# Controller_v6_1.net
KiCad netlist of a schematic drawn in Altium Designer
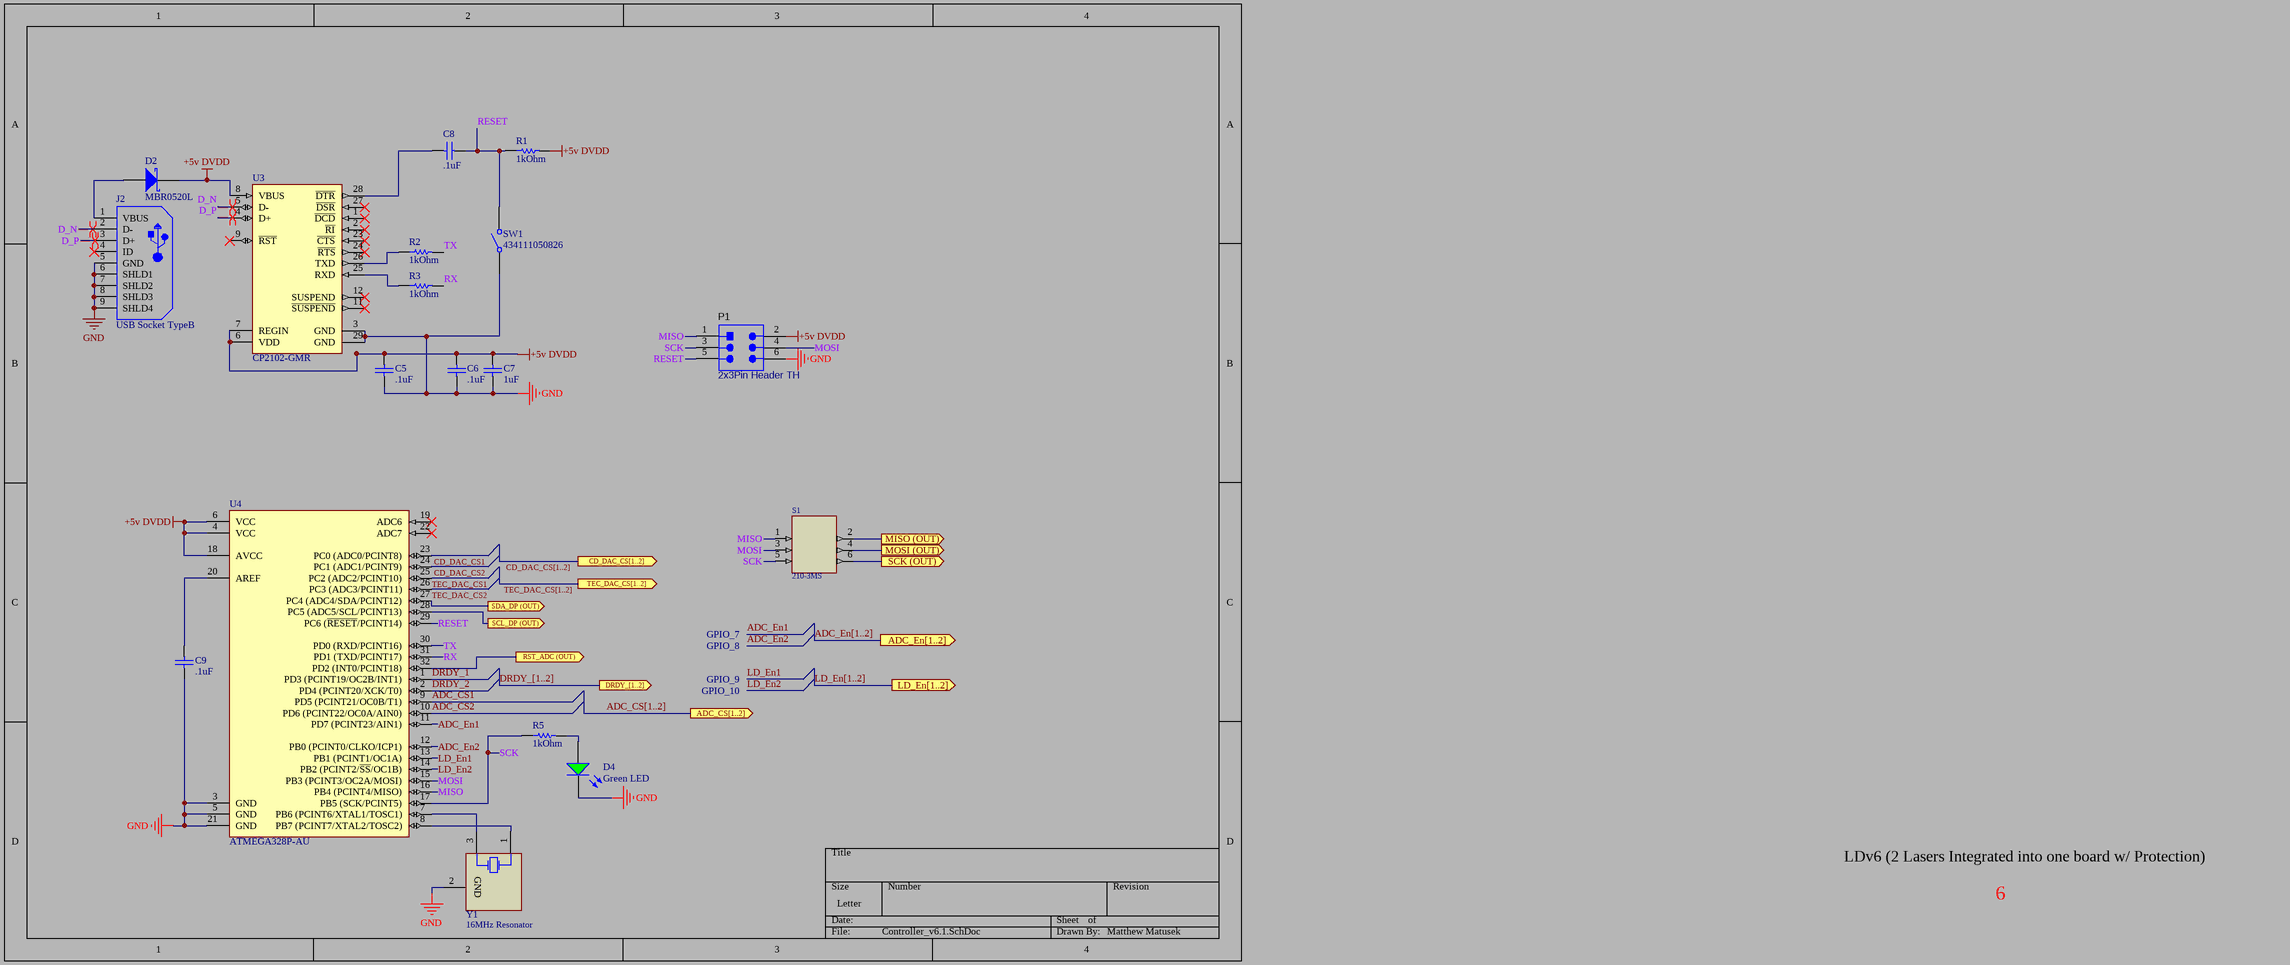
[diagram p0: Controller_v6.1.SchDoc]

(export (version "E")
  (design (tool "Eeschema 10.0.6"))
  (components
    (comp (ref "C5")
      (value ".1uF")
      (footprint "CAPC1608X90X35ML15T15")
      (fields
        (field (name "PART NUMBER") "06033D104MAT2A")
        (field (name "MANUFACTURER") "AVX Interconnect / Elco")
      )
      (libsource (lib "0.1uF Cap 0603") (part "CMP-2006-04192-1"))
    )
    (comp (ref "C6")
      (value ".1uF")
      (footprint "CAPC1608X90X35ML15T15")
      (fields
        (field (name "PART NUMBER") "06033D104MAT2A")
        (field (name "MANUFACTURER") "AVX Interconnect / Elco")
      )
      (libsource (lib "0.1uF Cap 0603") (part "CMP-2006-04192-1"))
    )
    (comp (ref "C7")
      (value "1uF")
      (footprint "CAPC1608X90X35ML15T15")
      (fields
        (field (name "PART NUMBER") "06036D105KAT2A")
        (field (name "MANUFACTURER") "AVX Interconnect / Elco")
      )
      (libsource (lib "1uF Cap 0603") (part "CMP-2006-04474-1"))
    )
    (comp (ref "C8")
      (value ".1uF")
      (footprint "CAPC1608X90X35ML15T15")
      (fields
        (field (name "PART NUMBER") "06033D104MAT2A")
        (field (name "MANUFACTURER") "AVX Interconnect / Elco")
      )
      (libsource (lib "0.1uF Cap 0603") (part "CMP-2006-04192-1"))
    )
    (comp (ref "C9")
      (value ".1uF")
      (footprint "CAPC1608X90X35ML15T15")
      (fields
        (field (name "PART NUMBER") "06033D104MAT2A")
        (field (name "MANUFACTURER") "AVX Interconnect / Elco")
      )
      (libsource (lib "0.1uF Cap 0603") (part "CMP-2006-04192-1"))
    )
    (comp (ref "D2")
      (value "MBR0520L")
      (footprint "ONSC-SOD-123-2-425-04_V")
      (description "Schottky Diode, 20V, 0.2A, 2-pin SOD-123, RoHS, Tape and Reel")
      (fields (field (name "MANUFACTURER") "FairchildSemiconductor"))
      (libsource (lib "Diode 20v 500mA 0603") (part "CMP-2000-04926-1"))
    )
    (comp (ref "D4")
      (value "Green LED")
      (footprint "LUMX-SML-LX0603_V")
      (description "LED Green Diode, 18 mcd, 50 mW, -25 to 85 degC, 2-Pin SMD, RoHS, Tape and Reel")
      (fields (field (name "MANUFACTURER") "Lumex") (field (name "PART NO") "SML-LX0603GW-TR"))
      (libsource (lib "Green LED 0603") (part "CMP-2000-07120-1"))
    )
    (comp (ref "J2")
      (value "USB Socket TypeB")
      (footprint "WE-65100516121_V")
      (description "MINI USB 2.0 SMT Type B 5 Contacts, 30 V, -40 to 105 degC, RoHS, Tape and Reel")
      (fields (field (name "MANUFACTURER") "Wuerth Elektronik"))
      (libsource (lib "CONN Mini USB TypeB") (part "CMP-2000-05576-1"))
    )
    (comp (ref "P1")
      (value "2x3Pin Header TH")
      (footprint "SMTC-TSW-103-07-G-D_V")
      (fields (field (name "MANUFACTURER") "Samtec-Inc."))
      (libsource (lib "2x3 Pin Header TH 2.54") (part "CMP-2000-07329-1"))
    )
    (comp (ref "R1")
      (value "1kOhm")
      (footprint "RESC1609X50X30LL8T20")
      (description "Chip Resistor, 1 KOhm, +/- 1%, 0.1 W, -55 to 155 degC, 0603 (1608 Metric), RoHS, Tape and Reel")
      (fields (field (name "MANUFACTURER") "Vishay Semiconductor"))
      (libsource (lib "1kOhm Res 0603") (part "CMP-1666-00003-4"))
    )
    (comp (ref "R2")
      (value "1kOhm")
      (footprint "RESC1609X50X30LL8T20")
      (description "Chip Resistor, 1 KOhm, +/- 1%, 0.1 W, -55 to 155 degC, 0603 (1608 Metric), RoHS, Tape and Reel")
      (fields (field (name "MANUFACTURER") "Vishay Semiconductor"))
      (libsource (lib "1kOhm Res 0603") (part "CMP-1666-00003-4"))
    )
    (comp (ref "R3")
      (value "1kOhm")
      (footprint "RESC1609X50X30LL8T20")
      (description "Chip Resistor, 1 KOhm, +/- 1%, 0.1 W, -55 to 155 degC, 0603 (1608 Metric), RoHS, Tape and Reel")
      (fields (field (name "MANUFACTURER") "Vishay Semiconductor"))
      (libsource (lib "1kOhm Res 0603") (part "CMP-1666-00003-4"))
    )
    (comp (ref "R5")
      (value "1kOhm")
      (footprint "RESC1609X50X30LL8T20")
      (description "Chip Resistor, 1 KOhm, +/- 1%, 0.1 W, -55 to 155 degC, 0603 (1608 Metric), RoHS, Tape and Reel")
      (fields (field (name "MANUFACTURER") "Vishay Semiconductor"))
      (libsource (lib "1kOhm Res 0603") (part "CMP-1666-00003-4"))
    )
    (comp (ref "S1")
      (value "210-3MS")
      (footprint "210-3MS")
      (description "3 Position Switch, TH")
      (libsource (lib "LDv6") (part "210-3MS"))
    )
    (comp (ref "SW1")
      (value "434111050826")
      (footprint "434111050826")
      (description "WS-TASV SMD Tact Switch 6.0X3.5 mm")
      (fields (field (name "MANUFACTURER") "Wuerth Elektronik"))
      (libsource (lib "2 Pad Tactile Switch") (part "CMP-1459-00003-1"))
    )
    (comp (ref "U3")
      (value "CP2102-GMR")
      (footprint "SLAB-QFN-28-3125x3125TP_M")
      (description "Single-Chip USB to URAT Bridge, 3.3 V, -40 to 85 degC, 28-Pin QFN, RoHS, Tape and Reel")
      (fields (field (name "MANUFACTURER") "Silicon Labs"))
      (libsource (lib "CP2102-GMR") (part "CMP-2000-04924-1"))
    )
    (comp (ref "U4")
      (value "ATMEGA328P-AU")
      (footprint "32A_L")
      (libsource (lib "ATMEGA328P-AU") (part "CMP-0095-00269-2"))
    )
    (comp (ref "Y1")
      (value "16MHz Resonator")
      (footprint "MURA-CSTCE_V-3_V")
      (fields (field (name "MANUFACTURER") "Murata") (field (name "PARTNUMBER") "CSTCE16M0V53-R0"))
      (libsource (lib "CER RES 16 MHz") (part "CMP-0588-00001-2"))
    )
  )
  (nets
    (net (code "1") (name "+5v DVDD") (class "Default")
      (node (ref "C5") (pin "2") (pinfunction "2_2") (pintype "passive"))
      (node (ref "C6") (pin "2") (pinfunction "2_2") (pintype "passive"))
      (node (ref "C7") (pin "2") (pinfunction "2_2") (pintype "passive"))
      (node (ref "D2") (pin "1") (pinfunction "K_1") (pintype "passive"))
      (node (ref "P1") (pin "2") (pinfunction "2_2") (pintype "passive"))
      (node (ref "R1") (pin "2") (pinfunction "2_2") (pintype "passive"))
      (node (ref "U3") (pin "6") (pinfunction "VDD_6") (pintype "power_in"))
      (node (ref "U3") (pin "7") (pinfunction "REGIN_7") (pintype "power_in"))
      (node (ref "U3") (pin "8") (pinfunction "VBUS_8") (pintype "input"))
      (node (ref "U4") (pin "18") (pinfunction "AVCC_18") (pintype "power_in"))
      (node (ref "U4") (pin "4") (pinfunction "VCC_4") (pintype "power_in"))
      (node (ref "U4") (pin "6") (pinfunction "VCC_6") (pintype "power_in"))
    )
    (net (code "2") (name "/ADC_CS1") (class "Default")
      (node (ref "U4") (pin "9") (pinfunction "PD5_(PCINT21/OC0B/T1)_9") (pintype "bidirectional"))
    )
    (net (code "3") (name "/ADC_CS2") (class "Default")
      (node (ref "U4") (pin "10") (pinfunction "PD6_(PCINT22/OC0A/AIN0)_10") (pintype "bidirectional"))
    )
    (net (code "5") (name "/ADC_En1") (class "Default")
      (node (ref "U4") (pin "11") (pinfunction "PD7_(PCINT23/AIN1)_11") (pintype "bidirectional"))
    )
    (net (code "6") (name "/ADC_En2") (class "Default")
      (node (ref "U4") (pin "12") (pinfunction "PB0_(PCINT0/CLKO/ICP1)_12") (pintype "bidirectional"))
    )
    (net (code "8") (name "/CD_DAC_CS1") (class "Default")
      (node (ref "U4") (pin "23") (pinfunction "PC0_(ADC0/PCINT8)_23") (pintype "bidirectional"))
    )
    (net (code "9") (name "/CD_DAC_CS2") (class "Default")
      (node (ref "U4") (pin "24") (pinfunction "PC1_(ADC1/PCINT9)_24") (pintype "bidirectional"))
    )
    (net (code "11") (name "/DRDY_1") (class "Default")
      (node (ref "U4") (pin "1") (pinfunction "PD3_(PCINT19/OC2B/INT1)_1") (pintype "bidirectional"))
    )
    (net (code "12") (name "/DRDY_2") (class "Default")
      (node (ref "U4") (pin "2") (pinfunction "PD4_(PCINT20/XCK/T0)_2") (pintype "bidirectional"))
    )
    (net (code "14") (name "/D_N") (class "Default")
      (node (ref "J2") (pin "2") (pinfunction "D-_2") (pintype "passive"))
      (node (ref "U3") (pin "5") (pinfunction "D-_5") (pintype "bidirectional"))
    )
    (net (code "15") (name "/D_P") (class "Default")
      (node (ref "J2") (pin "3") (pinfunction "D+_3") (pintype "passive"))
      (node (ref "U3") (pin "4") (pinfunction "D+_4") (pintype "bidirectional"))
    )
    (net (code "16") (name "/LD_En1") (class "Default")
      (node (ref "U4") (pin "13") (pinfunction "PB1_(PCINT1/OC1A)_13") (pintype "bidirectional"))
    )
    (net (code "17") (name "/LD_En2") (class "Default")
      (node (ref "U4") (pin "14") (pinfunction "PB2_(PCINT2/~{SS}/OC1B)_14") (pintype "bidirectional"))
    )
    (net (code "19") (name "/MISO") (class "Default")
      (node (ref "P1") (pin "1") (pinfunction "1_1") (pintype "passive"))
      (node (ref "S1") (pin "1") (pintype "input"))
      (node (ref "U4") (pin "16") (pinfunction "PB4_(PCINT4/MISO)_16") (pintype "bidirectional"))
    )
    (net (code "20") (name "/MISO (OUT)") (class "Default") (node (ref "S1") (pin "2") (pintype "output")))
    (net (code "21") (name "/MOSI") (class "Default")
      (node (ref "P1") (pin "4") (pinfunction "4_4") (pintype "passive"))
      (node (ref "S1") (pin "3") (pintype "input"))
      (node (ref "U4") (pin "15") (pinfunction "PB3_(PCINT3/OC2A/MOSI)_15") (pintype "bidirectional"))
    )
    (net (code "22") (name "/MOSI (OUT)") (class "Default") (node (ref "S1") (pin "4") (pintype "output")))
    (net (code "23") (name "/RESET") (class "Default")
      (node (ref "C8") (pin "2") (pinfunction "2_2") (pintype "passive"))
      (node (ref "P1") (pin "5") (pinfunction "5_5") (pintype "passive"))
      (node (ref "R1") (pin "1") (pinfunction "1_1") (pintype "passive"))
      (node (ref "SW1") (pin "2") (pinfunction "2_2") (pintype "passive"))
      (node (ref "U4") (pin "29") (pinfunction "PC6_(~{RESET}/PCINT14)_29") (pintype "bidirectional"))
    )
    (net (code "24") (name "/RST_ADC (OUT)") (class "Default")
      (node (ref "U4") (pin "32") (pinfunction "PD2_(INT0/PCINT18)_32") (pintype "bidirectional"))
    )
    (net (code "25") (name "/RX") (class "Default")
      (node (ref "R3") (pin "2") (pinfunction "2_2") (pintype "passive"))
      (node (ref "U4") (pin "31") (pinfunction "PD1_(TXD/PCINT17)_31") (pintype "bidirectional"))
    )
    (net (code "26") (name "/SCK") (class "Default")
      (node (ref "P1") (pin "3") (pinfunction "3_3") (pintype "passive"))
      (node (ref "R5") (pin "1") (pinfunction "1_1") (pintype "passive"))
      (node (ref "S1") (pin "5") (pintype "input"))
      (node (ref "U4") (pin "17") (pinfunction "PB5_(SCK/PCINT5)_17") (pintype "bidirectional"))
    )
    (net (code "27") (name "/SCK (OUT)") (class "Default") (node (ref "S1") (pin "6") (pintype "output")))
    (net (code "28") (name "/SCL_DP (OUT)") (class "Default")
      (node (ref "U4") (pin "28") (pinfunction "PC5_(ADC5/SCL/PCINT13)_28") (pintype "bidirectional"))
    )
    (net (code "29") (name "/SDA_DP (OUT)") (class "Default")
      (node (ref "U4") (pin "27") (pinfunction "PC4_(ADC4/SDA/PCINT12)_27") (pintype "bidirectional"))
    )
    (net (code "30") (name "/TEC_DAC_CS1") (class "Default")
      (node (ref "U4") (pin "25") (pinfunction "PC2_(ADC2/PCINT10)_25") (pintype "bidirectional"))
    )
    (net (code "31") (name "/TEC_DAC_CS2") (class "Default")
      (node (ref "U4") (pin "26") (pinfunction "PC3_(ADC3/PCINT11)_26") (pintype "bidirectional"))
    )
    (net (code "33") (name "/TX") (class "Default")
      (node (ref "R2") (pin "2") (pinfunction "2_2") (pintype "passive"))
      (node (ref "U4") (pin "30") (pinfunction "PD0_(RXD/PCINT16)_30") (pintype "bidirectional"))
    )
    (net (code "34") (name "GND") (class "Default")
      (node (ref "C5") (pin "1") (pinfunction "1_1") (pintype "passive"))
      (node (ref "C6") (pin "1") (pinfunction "1_1") (pintype "passive"))
      (node (ref "C7") (pin "1") (pinfunction "1_1") (pintype "passive"))
      (node (ref "C9") (pin "1") (pinfunction "1_1") (pintype "passive"))
      (node (ref "D4") (pin "2") (pinfunction "K_2") (pintype "passive"))
      (node (ref "J2") (pin "5") (pinfunction "GND_5") (pintype "power_in"))
      (node (ref "J2") (pin "6") (pinfunction "SHLD1_6") (pintype "passive"))
      (node (ref "J2") (pin "7") (pinfunction "SHLD2_7") (pintype "passive"))
      (node (ref "J2") (pin "8") (pinfunction "SHLD3_8") (pintype "passive"))
      (node (ref "J2") (pin "9") (pinfunction "SHLD4_9") (pintype "passive"))
      (node (ref "P1") (pin "6") (pinfunction "6_6") (pintype "passive"))
      (node (ref "SW1") (pin "1") (pinfunction "1_1") (pintype "passive"))
      (node (ref "U3") (pin "29") (pinfunction "GND_29") (pintype "power_in"))
      (node (ref "U3") (pin "3") (pinfunction "GND_3") (pintype "power_in"))
      (node (ref "U4") (pin "21") (pinfunction "GND_21") (pintype "power_in"))
      (node (ref "U4") (pin "3") (pinfunction "GND_3") (pintype "power_in"))
      (node (ref "U4") (pin "5") (pinfunction "GND_5") (pintype "power_in"))
      (node (ref "Y1") (pin "2") (pinfunction "GND_2") (pintype "power_in"))
    )
    (net (code "35") (name "Net-(D2-A)") (class "Default")
      (node (ref "D2") (pin "2") (pinfunction "A_2") (pintype "passive"))
      (node (ref "J2") (pin "1") (pinfunction "VBUS_1") (pintype "power_in"))
    )
    (net (code "36") (name "Net-(D4-A)") (class "Default")
      (node (ref "D4") (pin "1") (pinfunction "A_1") (pintype "passive"))
      (node (ref "R5") (pin "2") (pinfunction "2_2") (pintype "passive"))
    )
    (net (code "37") (name "Net-(U3-RXD)") (class "Default")
      (node (ref "R3") (pin "1") (pinfunction "1_1") (pintype "passive"))
      (node (ref "U3") (pin "25") (pinfunction "RXD_25") (pintype "input"))
    )
    (net (code "38") (name "Net-(U3-TXD)") (class "Default")
      (node (ref "R2") (pin "1") (pinfunction "1_1") (pintype "passive"))
      (node (ref "U3") (pin "26") (pinfunction "TXD_26") (pintype "output"))
    )
    (net (code "39") (name "Net-(U3-~{DTR})") (class "Default")
      (node (ref "C8") (pin "1") (pinfunction "1_1") (pintype "passive"))
      (node (ref "U3") (pin "28") (pinfunction "~{DTR}_28") (pintype "output"))
    )
    (net (code "40") (name "Net-(U4-AREF)") (class "Default")
      (node (ref "C9") (pin "2") (pinfunction "2_2") (pintype "passive"))
      (node (ref "U4") (pin "20") (pinfunction "AREF_20") (pintype "passive"))
    )
    (net (code "41") (name "Net-(U4-PB6_(PCINT6{slash}XTAL1{slash}TOSC1))") (class "Default")
      (node (ref "U4") (pin "7") (pinfunction "PB6_(PCINT6/XTAL1/TOSC1)_7") (pintype "bidirectional"))
      (node (ref "Y1") (pin "3") (pinfunction "C2_3") (pintype "passive"))
    )
    (net (code "42") (name "Net-(U4-PB7_(PCINT7{slash}XTAL2{slash}TOSC2))") (class "Default")
      (node (ref "U4") (pin "8") (pinfunction "PB7_(PCINT7/XTAL2/TOSC2)_8") (pintype "bidirectional"))
      (node (ref "Y1") (pin "1") (pinfunction "C1_1") (pintype "passive"))
    )
    (net (code "43") (name "unconnected-(J2-ID-Pad4)") (class "Default")
      (node (ref "J2") (pin "4") (pinfunction "ID_4") (pintype "passive+no_connect"))
    )
    (net (code "44") (name "unconnected-(U3-SUSPEND-Pad12)") (class "Default")
      (node (ref "U3") (pin "12") (pinfunction "SUSPEND_12") (pintype "output+no_connect"))
    )
    (net (code "45") (name "unconnected-(U3-~{CTS}-Pad23)") (class "Default")
      (node (ref "U3") (pin "23") (pinfunction "~{CTS}_23") (pintype "input+no_connect"))
    )
    (net (code "46") (name "unconnected-(U3-~{DCD}-Pad1)") (class "Default")
      (node (ref "U3") (pin "1") (pinfunction "~{DCD}_1") (pintype "input+no_connect"))
    )
    (net (code "47") (name "unconnected-(U3-~{DSR}-Pad27)") (class "Default")
      (node (ref "U3") (pin "27") (pinfunction "~{DSR}_27") (pintype "input+no_connect"))
    )
    (net (code "48") (name "unconnected-(U3-~{RI}-Pad2)") (class "Default")
      (node (ref "U3") (pin "2") (pinfunction "~{RI}_2") (pintype "input+no_connect"))
    )
    (net (code "49") (name "unconnected-(U3-~{RST}-Pad9)") (class "Default")
      (node (ref "U3") (pin "9") (pinfunction "~{RST}_9") (pintype "bidirectional+no_connect"))
    )
    (net (code "50") (name "unconnected-(U3-~{RTS}-Pad24)") (class "Default")
      (node (ref "U3") (pin "24") (pinfunction "~{RTS}_24") (pintype "output+no_connect"))
    )
    (net (code "51") (name "unconnected-(U3-~{SUSPEND}-Pad11)") (class "Default")
      (node (ref "U3") (pin "11") (pinfunction "~{SUSPEND}_11") (pintype "output+no_connect"))
    )
    (net (code "52") (name "unconnected-(U4-ADC6-Pad19)") (class "Default")
      (node (ref "U4") (pin "19") (pinfunction "ADC6_19") (pintype "input+no_connect"))
    )
    (net (code "53") (name "unconnected-(U4-ADC7-Pad22)") (class "Default")
      (node (ref "U4") (pin "22") (pinfunction "ADC7_22") (pintype "input+no_connect"))
    )
  )
)
